# UNOshield.net
KiCad netlist of a schematic drawn in Altium Designer
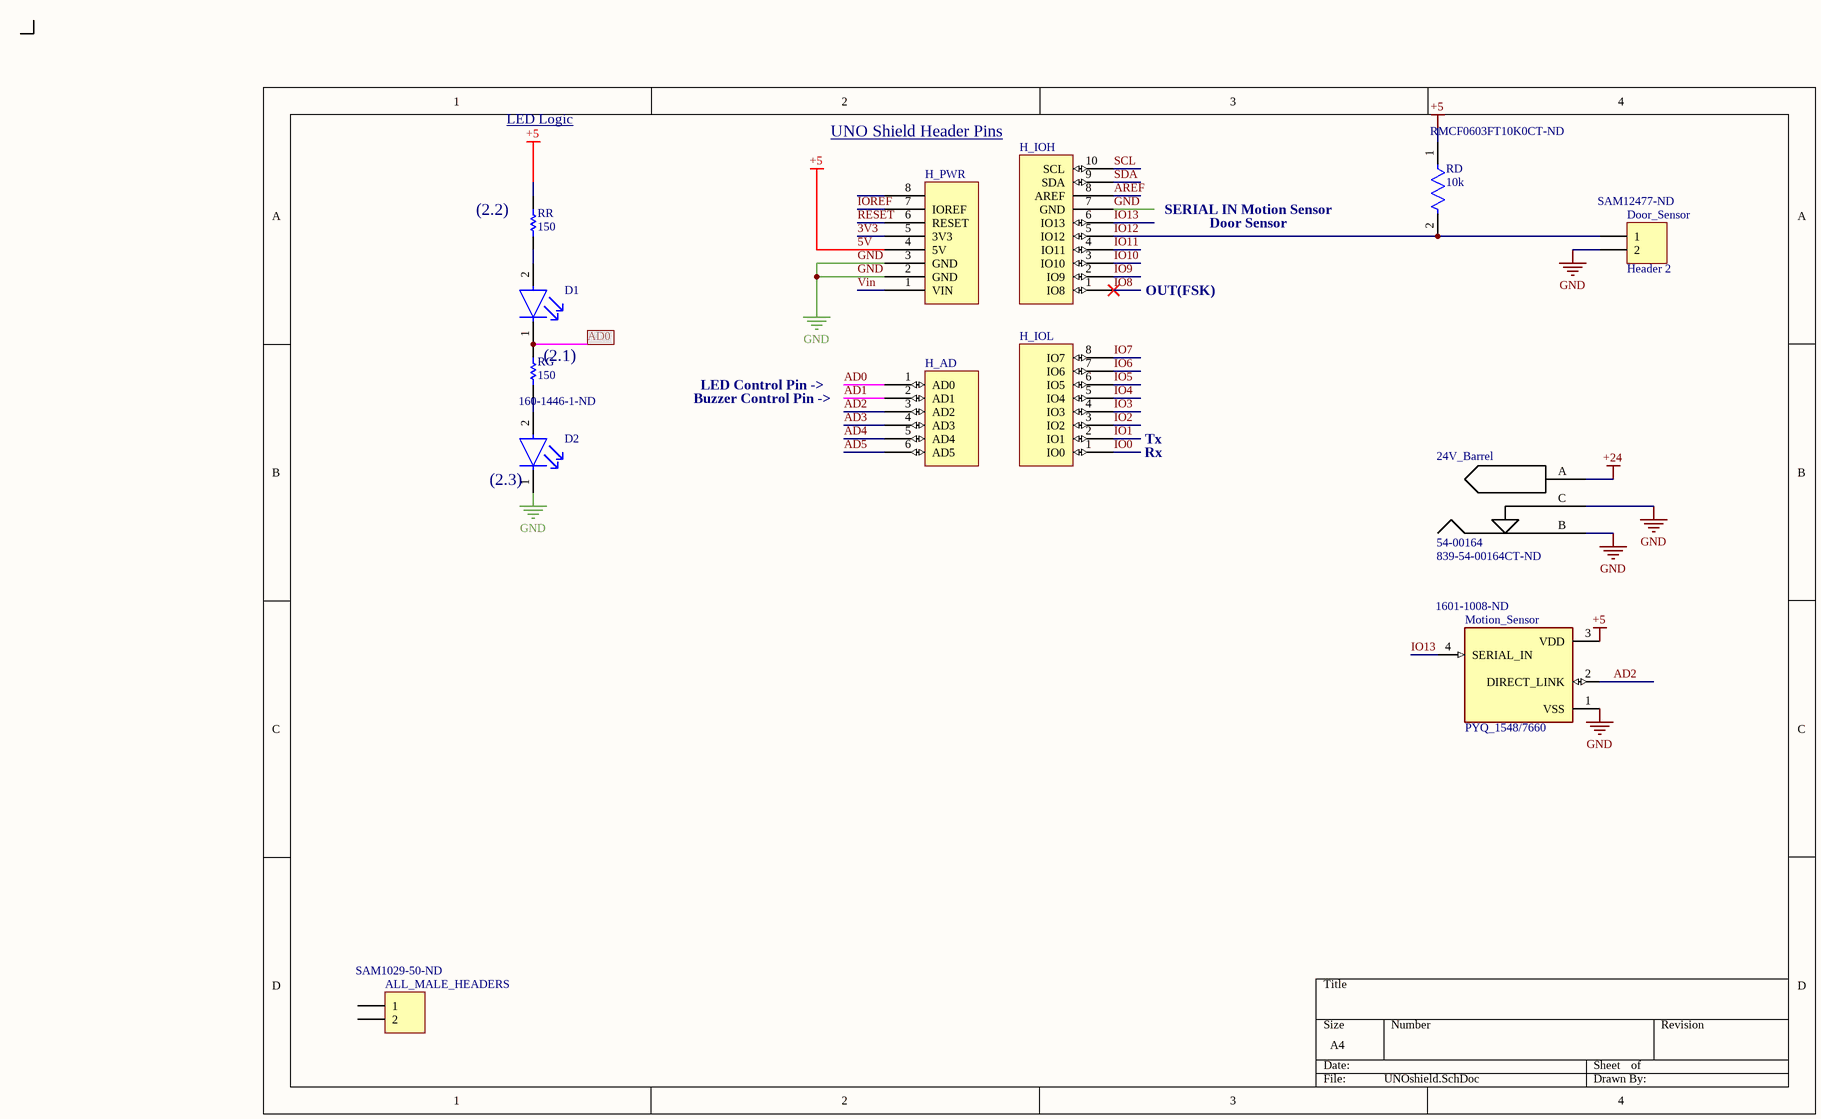
[diagram p0: UNOshield.SchDoc]

(export (version "E")
  (design (tool "Eeschema 10.0.6"))
  (components
    (comp (ref "24V_Barrel")
      (value "54-00164")
      (footprint "54-00164")
      (description "Power Barrel Connector Jack 2.10mm ID (0.083\"), 5.50mm OD (0.217\") Surface Mount, Right Angle")
      (fields
        (field (name "MANUFACTURER") "Tensility")
        (field (name "SUPPLIER PART NUMBER 1") "839-54-00164CT-ND")
      )
      (libsource (lib "Tensility_Barrel_Jacks") (part "54-00164"))
    )
    (comp (ref "ALL_MALE_HEADERS")
      (value "~")
      (footprint "HDR1X2")
      (fields
        (field (name "SUPPLIER PART NUMBER 1") "SAM1029-50-ND")
        (field (name "MANUFACTURER") "Samtec")
        (field (name "MANUFACTURER PART NUMBER") "TSW-150-07-G-S")
      )
      (libsource (lib "Miscellaneous Connectors") (part "Header 2"))
    )
    (comp (ref "D1")
      (value "LS R976-NR-1")
      (footprint "FP-LS_R976-MFG")
      (description "LED RED DIFFUSED 0805 SMD")
      (libsource (lib "Altium Content Vault") (part "8706943c75ba83719d021d2fdc84c58"))
    )
    (comp (ref "D2")
      (value "LTST-C191KGKT")
      (footprint "FP-LTST-C191KGKT-MFG")
      (description "Single Color LED, Ultra Bright Green, Water Clear, 1.1mm")
      (fields
        (field (name "SUPPLIER PART NUMBER 1") "160-1446-1-ND")
        (field (name "MANUFACTURER") "Vishay Lite-On")
      )
      (libsource (lib "Altium Content Vault") (part "8706943c75ba83719d021d2fdc84c58"))
    )
    (comp (ref "Door_Sensor")
      (value "Header 2")
      (footprint "HDR1X2")
      (fields
        (field (name "SUPPLIER PART NUMBER 1") "SAM12477-ND")
        (field (name "MANUFACTURER") "Samtec")
        (field (name "MANUFACTURER PART NUMBER") "CES-102-01-G-S")
        (field (name "PUBLISHER") "Altium Limited")
      )
      (libsource (lib "Miscellaneous Connectors") (part "Header 2"))
    )
    (comp (ref "H_AD")
      (value "AD")
      (footprint "Header:Header 6x1 8.5mm")
      (libsource (lib "Header") (part "AD"))
    )
    (comp (ref "H_IOH")
      (value "IOH")
      (footprint "Header:Header 10x1 8.5mm")
      (libsource (lib "Header") (part "IOH"))
    )
    (comp (ref "H_IOL") (value "IOL") (footprint "Header 8x1 8.5mm") (libsource (lib "Header") (part "IOL")))
    (comp (ref "H_PWR")
      (value "POWER_UNO")
      (footprint "Header 8x1 8.5mm")
      (libsource (lib "Header") (part "POWER_UNO"))
    )
    (comp (ref "Motion_Sensor")
      (value "PYQ_1548/7660")
      (footprint "TO254P940H440-4")
      (description "Low Power Digipyro Motion Sens")
      (fields
        (field (name "MF") "Excelitas Technologies")
        (field (name "MP") "PYQ 1548/7660")
        (field (name "SUPPLIER PART NUMBER 1") "1601-1008-ND")
      )
      (libsource (lib "PYQ_1548_7660") (part "PYQ_1548/7660"))
    )
    (comp (ref "RD")
      (value "10k")
      (footprint "FP-RC0603-0_55-IPC_C")
      (description "RES 10K OHM 1% 1/10W 0603")
      (fields
        (field (name "TOLERANCE") "1%")
        (field (name "SUPPLIER PART NUMBER 1") "RMCF0603FT10K0CT-ND")
        (field (name "MANUFACTURER") "Stackpole Electronics")
      )
      (libsource (lib "Altium Content Vault") (part "1029c3af85768c4190bb7ad29bc67b5"))
    )
    (comp (ref "RG")
      (value "150")
      (footprint "C0805")
      (fields
        (field (name "MANUFACTURER") "Yageo")
        (field (name "MANUFACTURER PART NUMBER") "RC0805FR-07150RL")
        (field (name "TOLERANCE") "1%")
      )
      (libsource (lib "Miscellaneous Devices") (part "Res1"))
    )
    (comp (ref "RR")
      (value "150")
      (footprint "C0805")
      (fields
        (field (name "MANUFACTURER") "Yageo")
        (field (name "MANUFACTURER PART NUMBER") "RC0805FR-07150RL")
        (field (name "TOLERANCE") "1%")
      )
      (libsource (lib "Miscellaneous Devices") (part "Res1"))
    )
  )
  (nets
    (net (code "1") (name "+5") (class "Default")
      (node (ref "H_PWR") (pin "4") (pinfunction "5V_4") (pintype "power_in"))
      (node (ref "Motion_Sensor") (pin "3") (pinfunction "VDD_3") (pintype "power_in"))
      (node (ref "RD") (pin "1") (pinfunction "1_1") (pintype "passive"))
      (node (ref "RR") (pin "2") (pinfunction "2_2") (pintype "passive"))
    )
    (net (code "2") (name "+24") (class "Default")
      (node (ref "24V_Barrel") (pin "A") (pinfunction "Pin/Center_A") (pintype "power_in"))
    )
    (net (code "3") (name "/3V3") (class "Default")
      (node (ref "H_PWR") (pin "5") (pinfunction "3V3_5") (pintype "power_in"))
    )
    (net (code "4") (name "/AD0") (class "Default")
      (node (ref "D1") (pin "1") (pinfunction "C_1") (pintype "passive"))
      (node (ref "H_AD") (pin "1") (pinfunction "AD0_1") (pintype "bidirectional"))
      (node (ref "RG") (pin "2") (pinfunction "2_2") (pintype "passive"))
    )
    (net (code "5") (name "/AD1") (class "Default")
      (node (ref "H_AD") (pin "2") (pinfunction "AD1_2") (pintype "bidirectional"))
    )
    (net (code "6") (name "/AD2") (class "Default")
      (node (ref "H_AD") (pin "3") (pinfunction "AD2_3") (pintype "bidirectional"))
      (node (ref "Motion_Sensor") (pin "2") (pinfunction "DIRECT_LINK_2") (pintype "bidirectional"))
    )
    (net (code "7") (name "/AD3") (class "Default")
      (node (ref "H_AD") (pin "4") (pinfunction "AD3_4") (pintype "bidirectional"))
    )
    (net (code "8") (name "/AD4") (class "Default")
      (node (ref "H_AD") (pin "5") (pinfunction "AD4_5") (pintype "bidirectional"))
    )
    (net (code "9") (name "/AD5") (class "Default")
      (node (ref "H_AD") (pin "6") (pinfunction "AD5_6") (pintype "bidirectional"))
    )
    (net (code "10") (name "/AREF") (class "Default")
      (node (ref "H_IOH") (pin "8") (pinfunction "AREF_8") (pintype "passive"))
    )
    (net (code "11") (name "/IO0") (class "Default")
      (node (ref "H_IOL") (pin "1") (pinfunction "IO0_1") (pintype "bidirectional"))
    )
    (net (code "12") (name "/IO1") (class "Default")
      (node (ref "H_IOL") (pin "2") (pinfunction "IO1_2") (pintype "bidirectional"))
    )
    (net (code "13") (name "/IO2") (class "Default")
      (node (ref "H_IOL") (pin "3") (pinfunction "IO2_3") (pintype "bidirectional"))
    )
    (net (code "14") (name "/IO3") (class "Default")
      (node (ref "H_IOL") (pin "4") (pinfunction "IO3_4") (pintype "bidirectional"))
    )
    (net (code "15") (name "/IO4") (class "Default")
      (node (ref "H_IOL") (pin "5") (pinfunction "IO4_5") (pintype "bidirectional"))
    )
    (net (code "16") (name "/IO5") (class "Default")
      (node (ref "H_IOL") (pin "6") (pinfunction "IO5_6") (pintype "bidirectional"))
    )
    (net (code "17") (name "/IO6") (class "Default")
      (node (ref "H_IOL") (pin "7") (pinfunction "IO6_7") (pintype "bidirectional"))
    )
    (net (code "18") (name "/IO7") (class "Default")
      (node (ref "H_IOL") (pin "8") (pinfunction "IO7_8") (pintype "bidirectional"))
    )
    (net (code "19") (name "/IO8") (class "Default")
      (node (ref "H_IOH") (pin "1") (pinfunction "IO8_1") (pintype "bidirectional+no_connect"))
    )
    (net (code "20") (name "/IO9") (class "Default")
      (node (ref "H_IOH") (pin "2") (pinfunction "IO9_2") (pintype "bidirectional"))
    )
    (net (code "21") (name "/IO10") (class "Default")
      (node (ref "H_IOH") (pin "3") (pinfunction "IO10_3") (pintype "bidirectional"))
    )
    (net (code "22") (name "/IO11") (class "Default")
      (node (ref "H_IOH") (pin "4") (pinfunction "IO11_4") (pintype "bidirectional"))
    )
    (net (code "23") (name "/IO12") (class "Default")
      (node (ref "Door_Sensor") (pin "1") (pinfunction "1_1") (pintype "passive"))
      (node (ref "H_IOH") (pin "5") (pinfunction "IO12_5") (pintype "bidirectional"))
      (node (ref "RD") (pin "2") (pinfunction "2_2") (pintype "passive"))
    )
    (net (code "24") (name "/IO13") (class "Default")
      (node (ref "H_IOH") (pin "6") (pinfunction "IO13_6") (pintype "bidirectional"))
      (node (ref "Motion_Sensor") (pin "4") (pinfunction "SERIAL_IN_4") (pintype "input"))
    )
    (net (code "25") (name "/IOREF") (class "Default")
      (node (ref "H_PWR") (pin "7") (pinfunction "IOREF_7") (pintype "power_in"))
    )
    (net (code "26") (name "/RESET") (class "Default")
      (node (ref "H_PWR") (pin "6") (pinfunction "RESET_6") (pintype "passive"))
    )
    (net (code "27") (name "/SCL") (class "Default")
      (node (ref "H_IOH") (pin "10") (pinfunction "SCL_10") (pintype "bidirectional"))
    )
    (net (code "28") (name "/SDA") (class "Default")
      (node (ref "H_IOH") (pin "9") (pinfunction "SDA_9") (pintype "bidirectional"))
    )
    (net (code "29") (name "/Vin") (class "Default")
      (node (ref "H_PWR") (pin "1") (pinfunction "VIN_1") (pintype "power_in"))
    )
    (net (code "30") (name "GND") (class "Default")
      (node (ref "24V_Barrel") (pin "B") (pintype "power_in"))
      (node (ref "24V_Barrel") (pin "C") (pinfunction "Sheath/Outer_C") (pintype "power_in"))
      (node (ref "D2") (pin "1") (pinfunction "C_1") (pintype "passive"))
      (node (ref "Door_Sensor") (pin "2") (pinfunction "2_2") (pintype "passive"))
      (node (ref "H_IOH") (pin "7") (pinfunction "GND_7") (pintype "power_in"))
      (node (ref "H_PWR") (pin "2") (pinfunction "GND_2") (pintype "power_in"))
      (node (ref "H_PWR") (pin "3") (pinfunction "GND_3") (pintype "power_in"))
      (node (ref "Motion_Sensor") (pin "1") (pinfunction "VSS_1") (pintype "power_in"))
    )
    (net (code "31") (name "Net-(D1-A)") (class "Default")
      (node (ref "D1") (pin "2") (pinfunction "A_2") (pintype "passive"))
      (node (ref "RR") (pin "1") (pinfunction "1_1") (pintype "passive"))
    )
    (net (code "32") (name "Net-(D2-A)") (class "Default")
      (node (ref "D2") (pin "2") (pinfunction "A_2") (pintype "passive"))
      (node (ref "RG") (pin "1") (pinfunction "1_1") (pintype "passive"))
    )
    (net (code "33") (name "unconnected-(ALL_MALE_HEADERS-Pad1)") (class "Default")
      (node (ref "ALL_MALE_HEADERS") (pin "1") (pinfunction "1_1") (pintype "passive"))
    )
    (net (code "34") (name "unconnected-(ALL_MALE_HEADERS-Pad2)") (class "Default")
      (node (ref "ALL_MALE_HEADERS") (pin "2") (pinfunction "2_2") (pintype "passive"))
    )
    (net (code "35") (name "unconnected-(H_PWR-Pad8)") (class "Default")
      (node (ref "H_PWR") (pin "8") (pintype "passive"))
    )
  )
)
